# board.net
KiCad netlist of a schematic drawn in EAGLE
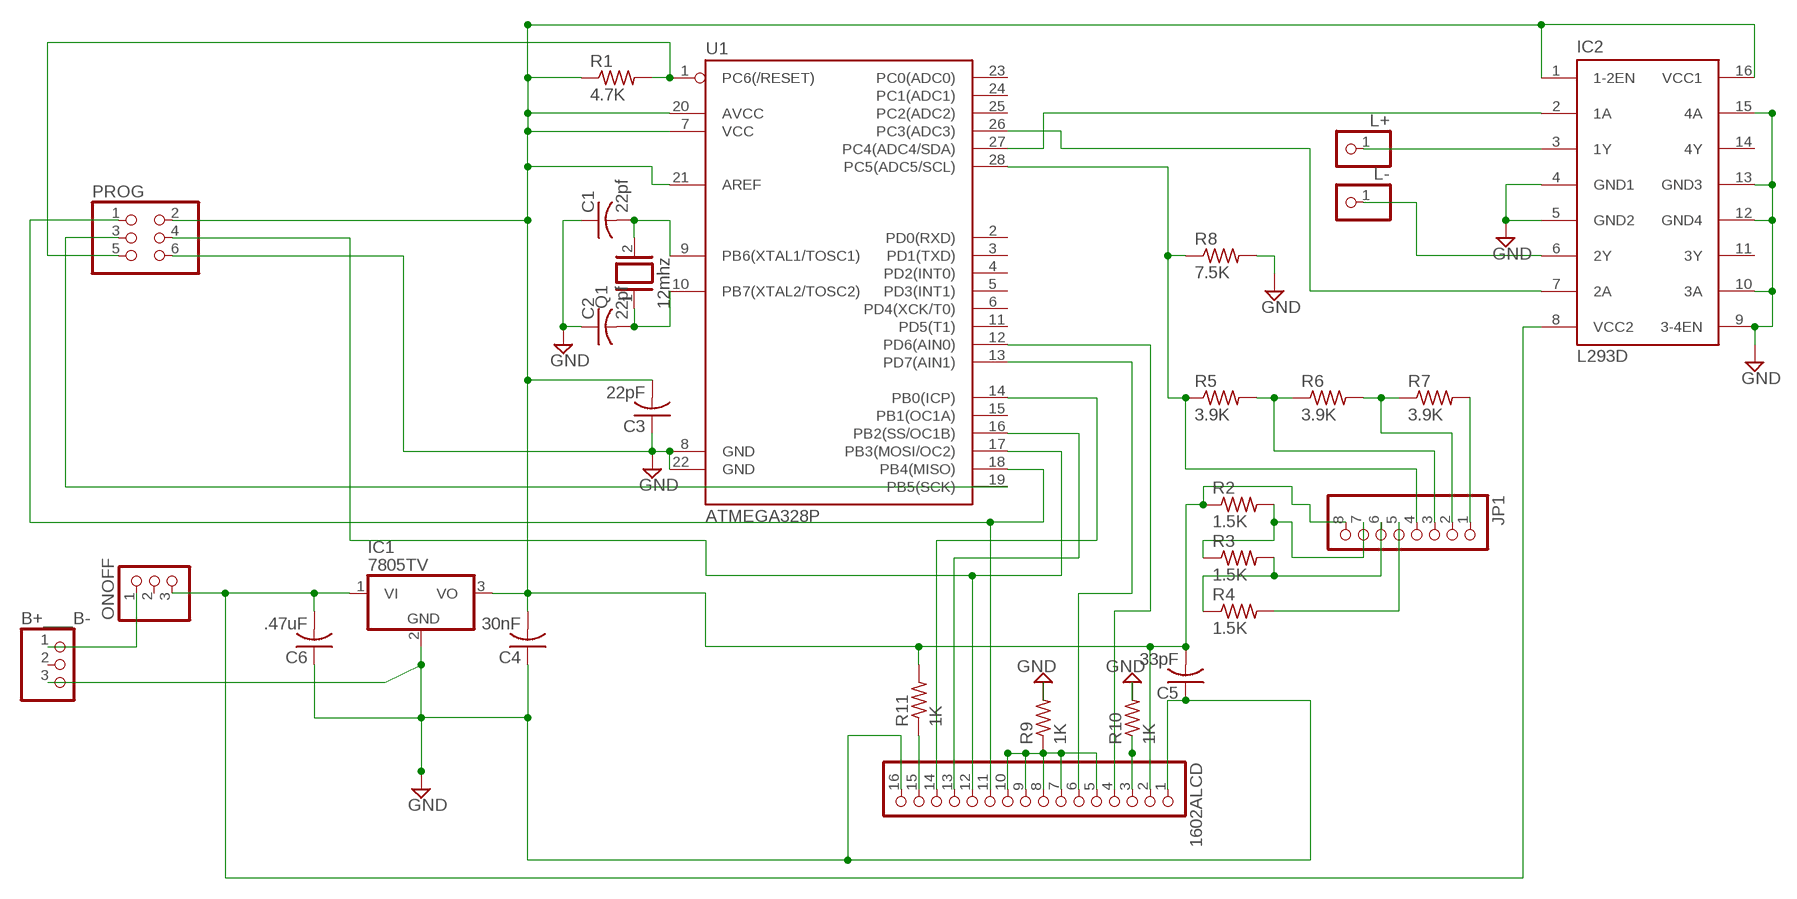
[diagram p0: schematic, sheet 1]

(export (version "E")
  (design (tool "Eeschema 10.0.6"))
  (components
    (comp (ref "1602ALCD")
      (value "PINHD-1X16")
      (footprint "eagle-import:1X16")
      (libsource (lib "eagle-import") (part "PINHD-1X16"))
    )
    (comp (ref "B+___B-")
      (value "PINHD-1X3")
      (footprint "eagle-import:1X03")
      (libsource (lib "eagle-import") (part "PINHD-1X3"))
    )
    (comp (ref "C1")
      (value "22pf")
      (footprint "eagle-import:C050-024X044")
      (libsource (lib "eagle-import") (part "C-US050-024X044"))
    )
    (comp (ref "C2")
      (value "22pf")
      (footprint "eagle-import:C050-024X044")
      (libsource (lib "eagle-import") (part "C-US050-024X044"))
    )
    (comp (ref "C3")
      (value "22pF")
      (footprint "eagle-import:C025-025X050")
      (libsource (lib "eagle-import") (part "resistor_C-US025-025X050"))
    )
    (comp (ref "C4")
      (value "30nF")
      (footprint "eagle-import:C025-025X050")
      (libsource (lib "eagle-import") (part "resistor_C-US025-025X050"))
    )
    (comp (ref "C5")
      (value "33pF")
      (footprint "eagle-import:C025-025X050")
      (libsource (lib "eagle-import") (part "resistor_C-US025-025X050"))
    )
    (comp (ref "C6")
      (value ".47uF")
      (footprint "eagle-import:C025-025X050")
      (libsource (lib "eagle-import") (part "resistor_C-US025-025X050"))
    )
    (comp (ref "IC1")
      (value "7805TV")
      (footprint "eagle-import:TO220V")
      (libsource (lib "eagle-import") (part "78TV05"))
    )
    (comp (ref "IC2")
      (value "L293D")
      (footprint "eagle-import:DIL16")
      (libsource (lib "eagle-import") (part "L293D"))
    )
    (comp (ref "JP1")
      (value "PINHD-1X8")
      (footprint "eagle-import:1X08")
      (libsource (lib "eagle-import") (part "PINHD-1X8"))
    )
    (comp (ref "L+")
      (value "PINHD-1X1")
      (footprint "eagle-import:1X01")
      (libsource (lib "eagle-import") (part "PINHD-1X1"))
    )
    (comp (ref "L-")
      (value "PINHD-1X1")
      (footprint "eagle-import:1X01")
      (libsource (lib "eagle-import") (part "PINHD-1X1"))
    )
    (comp (ref "ONOFF")
      (value "PINHD-1X3")
      (footprint "eagle-import:1X03")
      (libsource (lib "eagle-import") (part "PINHD-1X3"))
    )
    (comp (ref "PROG")
      (value "PINHD-2X3")
      (footprint "eagle-import:2X03")
      (libsource (lib "eagle-import") (part "PINHD-2X3"))
    )
    (comp (ref "Q1")
      (value "12mhz")
      (footprint "eagle-import:QS")
      (libsource (lib "eagle-import") (part "XTAL/S"))
    )
    (comp (ref "R1")
      (value "4.7K")
      (footprint "eagle-import:0207_7")
      (libsource (lib "eagle-import") (part "R-US_0207/7"))
    )
    (comp (ref "R2")
      (value "1.5K")
      (footprint "eagle-import:0207_7")
      (libsource (lib "eagle-import") (part "R-US_0207/7"))
    )
    (comp (ref "R3")
      (value "1.5K")
      (footprint "eagle-import:0207_7")
      (libsource (lib "eagle-import") (part "R-US_0207/7"))
    )
    (comp (ref "R4")
      (value "1.5K")
      (footprint "eagle-import:0207_7")
      (libsource (lib "eagle-import") (part "R-US_0207/7"))
    )
    (comp (ref "R5")
      (value "3.9K")
      (footprint "eagle-import:0207_7")
      (libsource (lib "eagle-import") (part "R-US_0207/7"))
    )
    (comp (ref "R6")
      (value "3.9K")
      (footprint "eagle-import:0207_7")
      (libsource (lib "eagle-import") (part "R-US_0207/7"))
    )
    (comp (ref "R7")
      (value "3.9K")
      (footprint "eagle-import:0207_7")
      (libsource (lib "eagle-import") (part "R-US_0207/7"))
    )
    (comp (ref "R8")
      (value "7.5K")
      (footprint "eagle-import:0207_7")
      (libsource (lib "eagle-import") (part "R-US_0207/7"))
    )
    (comp (ref "R9")
      (value "1K")
      (footprint "eagle-import:0207_7")
      (libsource (lib "eagle-import") (part "R-US_0207/7"))
    )
    (comp (ref "R10")
      (value "1K")
      (footprint "eagle-import:0207_7")
      (libsource (lib "eagle-import") (part "R-US_0207/7"))
    )
    (comp (ref "R11")
      (value "1K")
      (footprint "eagle-import:0207_7")
      (libsource (lib "eagle-import") (part "R-US_0207/7"))
    )
    (comp (ref "U1")
      (value "ATMEGA328P")
      (footprint "eagle-import:DIL28-3")
      (libsource (lib "eagle-import") (part "ATMEGA328P_PDIP"))
    )
  )
  (nets
    (net (code "1") (name "GND") (class "Default")
      (node (ref "1602ALCD") (pin "1") (pinfunction "1_1") (pintype "passive"))
      (node (ref "1602ALCD") (pin "16") (pinfunction "16_16") (pintype "passive"))
      (node (ref "B+___B-") (pin "3") (pinfunction "3_3") (pintype "passive"))
      (node (ref "C1") (pin "1") (pinfunction "1_1") (pintype "passive"))
      (node (ref "C2") (pin "1") (pinfunction "1_1") (pintype "passive"))
      (node (ref "C3") (pin "1") (pinfunction "1_1") (pintype "passive"))
      (node (ref "C4") (pin "1") (pinfunction "1_1") (pintype "passive"))
      (node (ref "C5") (pin "1") (pinfunction "1_1") (pintype "passive"))
      (node (ref "C6") (pin "1") (pinfunction "1_1") (pintype "passive"))
      (node (ref "IC1") (pin "2") (pinfunction "GND_2") (pintype "passive"))
      (node (ref "IC2") (pin "10") (pinfunction "3A_10") (pintype "input"))
      (node (ref "IC2") (pin "12") (pinfunction "GND4_12") (pintype "power_in"))
      (node (ref "IC2") (pin "13") (pinfunction "GND3_13") (pintype "power_in"))
      (node (ref "IC2") (pin "15") (pinfunction "4A_15") (pintype "input"))
      (node (ref "IC2") (pin "4") (pinfunction "GND1_4") (pintype "power_in"))
      (node (ref "IC2") (pin "5") (pinfunction "GND2_5") (pintype "power_in"))
      (node (ref "IC2") (pin "9") (pinfunction "3-4EN_9") (pintype "input"))
      (node (ref "PROG") (pin "6") (pinfunction "6_6") (pintype "passive"))
      (node (ref "R10") (pin "2") (pinfunction "2_2") (pintype "passive"))
      (node (ref "R8") (pin "2") (pinfunction "2_2") (pintype "passive"))
      (node (ref "R9") (pin "2") (pinfunction "2_2") (pintype "passive"))
      (node (ref "U1") (pin "22") (pinfunction "GND_22") (pintype "bidirectional"))
      (node (ref "U1") (pin "8") (pinfunction "GND_8") (pintype "bidirectional"))
    )
    (net (code "2") (name "Net-(1602ALCD-Pad3)") (class "Default")
      (node (ref "1602ALCD") (pin "3") (pinfunction "3_3") (pintype "passive"))
      (node (ref "R10") (pin "1") (pinfunction "1_1") (pintype "passive"))
    )
    (net (code "3") (name "Net-(1602ALCD-Pad10)") (class "Default")
      (node (ref "1602ALCD") (pin "10") (pinfunction "10_10") (pintype "passive"))
      (node (ref "1602ALCD") (pin "5") (pinfunction "5_5") (pintype "passive"))
      (node (ref "1602ALCD") (pin "7") (pinfunction "7_7") (pintype "passive"))
      (node (ref "1602ALCD") (pin "8") (pinfunction "8_8") (pintype "passive"))
      (node (ref "1602ALCD") (pin "9") (pinfunction "9_9") (pintype "passive"))
      (node (ref "R9") (pin "1") (pinfunction "1_1") (pintype "passive"))
    )
    (net (code "4") (name "Net-(1602ALCD-Pad15)") (class "Default")
      (node (ref "1602ALCD") (pin "15") (pinfunction "15_15") (pintype "passive"))
      (node (ref "R11") (pin "1") (pinfunction "1_1") (pintype "passive"))
    )
    (net (code "5") (name "Net-(B+___B--Pad1)") (class "Default")
      (node (ref "B+___B-") (pin "1") (pinfunction "1_1") (pintype "passive"))
      (node (ref "ONOFF") (pin "1") (pinfunction "1_1") (pintype "passive"))
    )
    (net (code "6") (name "Net-(IC1-VI)") (class "Default")
      (node (ref "C6") (pin "2") (pinfunction "2_2") (pintype "passive"))
      (node (ref "IC1") (pin "1") (pinfunction "VI_1") (pintype "input"))
      (node (ref "IC2") (pin "8") (pinfunction "VCC2_8") (pintype "power_in"))
      (node (ref "ONOFF") (pin "3") (pinfunction "3_3") (pintype "passive"))
    )
    (net (code "7") (name "Net-(IC1-VO)") (class "Default")
      (node (ref "1602ALCD") (pin "2") (pinfunction "2_2") (pintype "passive"))
      (node (ref "C3") (pin "2") (pinfunction "2_2") (pintype "passive"))
      (node (ref "C4") (pin "2") (pinfunction "2_2") (pintype "passive"))
      (node (ref "C5") (pin "2") (pinfunction "2_2") (pintype "passive"))
      (node (ref "IC1") (pin "3") (pinfunction "VO_3") (pintype "passive"))
      (node (ref "IC2") (pin "1") (pinfunction "1-2EN_1") (pintype "input"))
      (node (ref "IC2") (pin "16") (pinfunction "VCC1_16") (pintype "power_in"))
      (node (ref "JP1") (pin "8") (pinfunction "8_8") (pintype "passive"))
      (node (ref "PROG") (pin "2") (pinfunction "2_2") (pintype "passive"))
      (node (ref "R1") (pin "1") (pinfunction "1_1") (pintype "passive"))
      (node (ref "R11") (pin "2") (pinfunction "2_2") (pintype "passive"))
      (node (ref "R2") (pin "1") (pinfunction "1_1") (pintype "passive"))
      (node (ref "U1") (pin "20") (pinfunction "AVCC_20") (pintype "bidirectional"))
      (node (ref "U1") (pin "21") (pinfunction "AREF_21") (pintype "bidirectional"))
      (node (ref "U1") (pin "7") (pinfunction "VCC_7") (pintype "bidirectional"))
    )
    (net (code "8") (name "Net-(IC2-1A)") (class "Default")
      (node (ref "IC2") (pin "2") (pinfunction "1A_2") (pintype "input"))
      (node (ref "U1") (pin "27") (pinfunction "PC4(ADC4/SDA)_27") (pintype "bidirectional"))
    )
    (net (code "9") (name "Net-(IC2-1Y)") (class "Default")
      (node (ref "IC2") (pin "3") (pinfunction "1Y_3") (pintype "output"))
      (node (ref "L+") (pin "1") (pinfunction "1_1") (pintype "passive"))
    )
    (net (code "10") (name "Net-(IC2-2A)") (class "Default")
      (node (ref "IC2") (pin "7") (pinfunction "2A_7") (pintype "input"))
      (node (ref "U1") (pin "26") (pinfunction "PC3(ADC3)_26") (pintype "bidirectional"))
    )
    (net (code "11") (name "Net-(IC2-2Y)") (class "Default")
      (node (ref "IC2") (pin "6") (pinfunction "2Y_6") (pintype "output"))
      (node (ref "L-") (pin "1") (pinfunction "1_1") (pintype "passive"))
    )
    (net (code "12") (name "Net-(JP1-Pad1)") (class "Default")
      (node (ref "JP1") (pin "1") (pinfunction "1_1") (pintype "passive"))
      (node (ref "R7") (pin "2") (pinfunction "2_2") (pintype "passive"))
    )
    (net (code "13") (name "Net-(JP1-Pad2)") (class "Default")
      (node (ref "JP1") (pin "2") (pinfunction "2_2") (pintype "passive"))
      (node (ref "R6") (pin "2") (pinfunction "2_2") (pintype "passive"))
      (node (ref "R7") (pin "1") (pinfunction "1_1") (pintype "passive"))
    )
    (net (code "14") (name "Net-(JP1-Pad3)") (class "Default")
      (node (ref "JP1") (pin "3") (pinfunction "3_3") (pintype "passive"))
      (node (ref "R5") (pin "2") (pinfunction "2_2") (pintype "passive"))
      (node (ref "R6") (pin "1") (pinfunction "1_1") (pintype "passive"))
    )
    (net (code "15") (name "Net-(JP1-Pad5)") (class "Default")
      (node (ref "JP1") (pin "5") (pinfunction "5_5") (pintype "passive"))
      (node (ref "R4") (pin "2") (pinfunction "2_2") (pintype "passive"))
    )
    (net (code "16") (name "Net-(JP1-Pad6)") (class "Default")
      (node (ref "JP1") (pin "6") (pinfunction "6_6") (pintype "passive"))
      (node (ref "R3") (pin "2") (pinfunction "2_2") (pintype "passive"))
      (node (ref "R4") (pin "1") (pinfunction "1_1") (pintype "passive"))
    )
    (net (code "17") (name "Net-(JP1-Pad7)") (class "Default")
      (node (ref "JP1") (pin "7") (pinfunction "7_7") (pintype "passive"))
      (node (ref "R2") (pin "2") (pinfunction "2_2") (pintype "passive"))
      (node (ref "R3") (pin "1") (pinfunction "1_1") (pintype "passive"))
    )
    (net (code "18") (name "Net-(U1-PB0(ICP))") (class "Default")
      (node (ref "1602ALCD") (pin "14") (pinfunction "14_14") (pintype "passive"))
      (node (ref "U1") (pin "14") (pinfunction "PB0(ICP)_14") (pintype "bidirectional"))
    )
    (net (code "19") (name "Net-(U1-PB2(SS{slash}OC1B))") (class "Default")
      (node (ref "1602ALCD") (pin "13") (pinfunction "13_13") (pintype "passive"))
      (node (ref "U1") (pin "16") (pinfunction "PB2(SS/OC1B)_16") (pintype "bidirectional"))
    )
    (net (code "20") (name "Net-(U1-PB3(MOSI{slash}OC2))") (class "Default")
      (node (ref "1602ALCD") (pin "12") (pinfunction "12_12") (pintype "passive"))
      (node (ref "PROG") (pin "4") (pinfunction "4_4") (pintype "passive"))
      (node (ref "U1") (pin "17") (pinfunction "PB3(MOSI/OC2)_17") (pintype "bidirectional"))
    )
    (net (code "21") (name "Net-(U1-PB4(MISO))") (class "Default")
      (node (ref "1602ALCD") (pin "11") (pinfunction "11_11") (pintype "passive"))
      (node (ref "PROG") (pin "1") (pinfunction "1_1") (pintype "passive"))
      (node (ref "U1") (pin "18") (pinfunction "PB4(MISO)_18") (pintype "bidirectional"))
    )
    (net (code "22") (name "Net-(U1-PB5(SCK))") (class "Default")
      (node (ref "PROG") (pin "3") (pinfunction "3_3") (pintype "passive"))
      (node (ref "U1") (pin "19") (pinfunction "PB5(SCK)_19") (pintype "bidirectional"))
    )
    (net (code "23") (name "Net-(U1-PB6(XTAL1{slash}TOSC1))") (class "Default")
      (node (ref "C1") (pin "2") (pinfunction "2_2") (pintype "passive"))
      (node (ref "Q1") (pin "2") (pinfunction "2_2") (pintype "passive"))
      (node (ref "U1") (pin "9") (pinfunction "PB6(XTAL1/TOSC1)_9") (pintype "bidirectional"))
    )
    (net (code "24") (name "Net-(U1-PB7(XTAL2{slash}TOSC2))") (class "Default")
      (node (ref "C2") (pin "2") (pinfunction "2_2") (pintype "passive"))
      (node (ref "Q1") (pin "1") (pinfunction "1_1") (pintype "passive"))
      (node (ref "U1") (pin "10") (pinfunction "PB7(XTAL2/TOSC2)_10") (pintype "bidirectional"))
    )
    (net (code "25") (name "Net-(U1-PC5(ADC5{slash}SCL))") (class "Default")
      (node (ref "JP1") (pin "4") (pinfunction "4_4") (pintype "passive"))
      (node (ref "R5") (pin "1") (pinfunction "1_1") (pintype "passive"))
      (node (ref "R8") (pin "1") (pinfunction "1_1") (pintype "passive"))
      (node (ref "U1") (pin "28") (pinfunction "PC5(ADC5/SCL)_28") (pintype "bidirectional"))
    )
    (net (code "26") (name "Net-(U1-PC6({slash}RESET))") (class "Default")
      (node (ref "PROG") (pin "5") (pinfunction "5_5") (pintype "passive"))
      (node (ref "R1") (pin "2") (pinfunction "2_2") (pintype "passive"))
      (node (ref "U1") (pin "1") (pinfunction "PC6(/RESET)_1") (pintype "bidirectional"))
    )
    (net (code "27") (name "Net-(U1-PD6(AIN0))") (class "Default")
      (node (ref "1602ALCD") (pin "4") (pinfunction "4_4") (pintype "passive"))
      (node (ref "U1") (pin "12") (pinfunction "PD6(AIN0)_12") (pintype "bidirectional"))
    )
    (net (code "28") (name "Net-(U1-PD7(AIN1))") (class "Default")
      (node (ref "1602ALCD") (pin "6") (pinfunction "6_6") (pintype "passive"))
      (node (ref "U1") (pin "13") (pinfunction "PD7(AIN1)_13") (pintype "bidirectional"))
    )
    (net (code "29") (name "unconnected-(B+___B--Pad2)") (class "Default")
      (node (ref "B+___B-") (pin "2") (pinfunction "2_2") (pintype "passive"))
    )
    (net (code "30") (name "unconnected-(IC2-3Y-Pad11)") (class "Default")
      (node (ref "IC2") (pin "11") (pinfunction "3Y_11") (pintype "output"))
    )
    (net (code "31") (name "unconnected-(IC2-4Y-Pad14)") (class "Default")
      (node (ref "IC2") (pin "14") (pinfunction "4Y_14") (pintype "output"))
    )
    (net (code "32") (name "unconnected-(ONOFF-Pad2)") (class "Default")
      (node (ref "ONOFF") (pin "2") (pinfunction "2_2") (pintype "passive"))
    )
    (net (code "33") (name "unconnected-(U1-PB1(OC1A)-Pad15)") (class "Default")
      (node (ref "U1") (pin "15") (pinfunction "PB1(OC1A)_15") (pintype "bidirectional"))
    )
    (net (code "34") (name "unconnected-(U1-PC0(ADC0)-Pad23)") (class "Default")
      (node (ref "U1") (pin "23") (pinfunction "PC0(ADC0)_23") (pintype "bidirectional"))
    )
    (net (code "35") (name "unconnected-(U1-PC1(ADC1)-Pad24)") (class "Default")
      (node (ref "U1") (pin "24") (pinfunction "PC1(ADC1)_24") (pintype "bidirectional"))
    )
    (net (code "36") (name "unconnected-(U1-PC2(ADC2)-Pad25)") (class "Default")
      (node (ref "U1") (pin "25") (pinfunction "PC2(ADC2)_25") (pintype "bidirectional"))
    )
    (net (code "37") (name "unconnected-(U1-PD0(RXD)-Pad2)") (class "Default")
      (node (ref "U1") (pin "2") (pinfunction "PD0(RXD)_2") (pintype "bidirectional"))
    )
    (net (code "38") (name "unconnected-(U1-PD1(TXD)-Pad3)") (class "Default")
      (node (ref "U1") (pin "3") (pinfunction "PD1(TXD)_3") (pintype "bidirectional"))
    )
    (net (code "39") (name "unconnected-(U1-PD2(INT0)-Pad4)") (class "Default")
      (node (ref "U1") (pin "4") (pinfunction "PD2(INT0)_4") (pintype "bidirectional"))
    )
    (net (code "40") (name "unconnected-(U1-PD3(INT1)-Pad5)") (class "Default")
      (node (ref "U1") (pin "5") (pinfunction "PD3(INT1)_5") (pintype "bidirectional"))
    )
    (net (code "41") (name "unconnected-(U1-PD4(XCK{slash}T0)-Pad6)") (class "Default")
      (node (ref "U1") (pin "6") (pinfunction "PD4(XCK/T0)_6") (pintype "bidirectional"))
    )
    (net (code "42") (name "unconnected-(U1-PD5(T1)-Pad11)") (class "Default")
      (node (ref "U1") (pin "11") (pinfunction "PD5(T1)_11") (pintype "bidirectional"))
    )
  )
)
